# Sheet1.net
KiCad netlist of a schematic drawn in Altium Designer
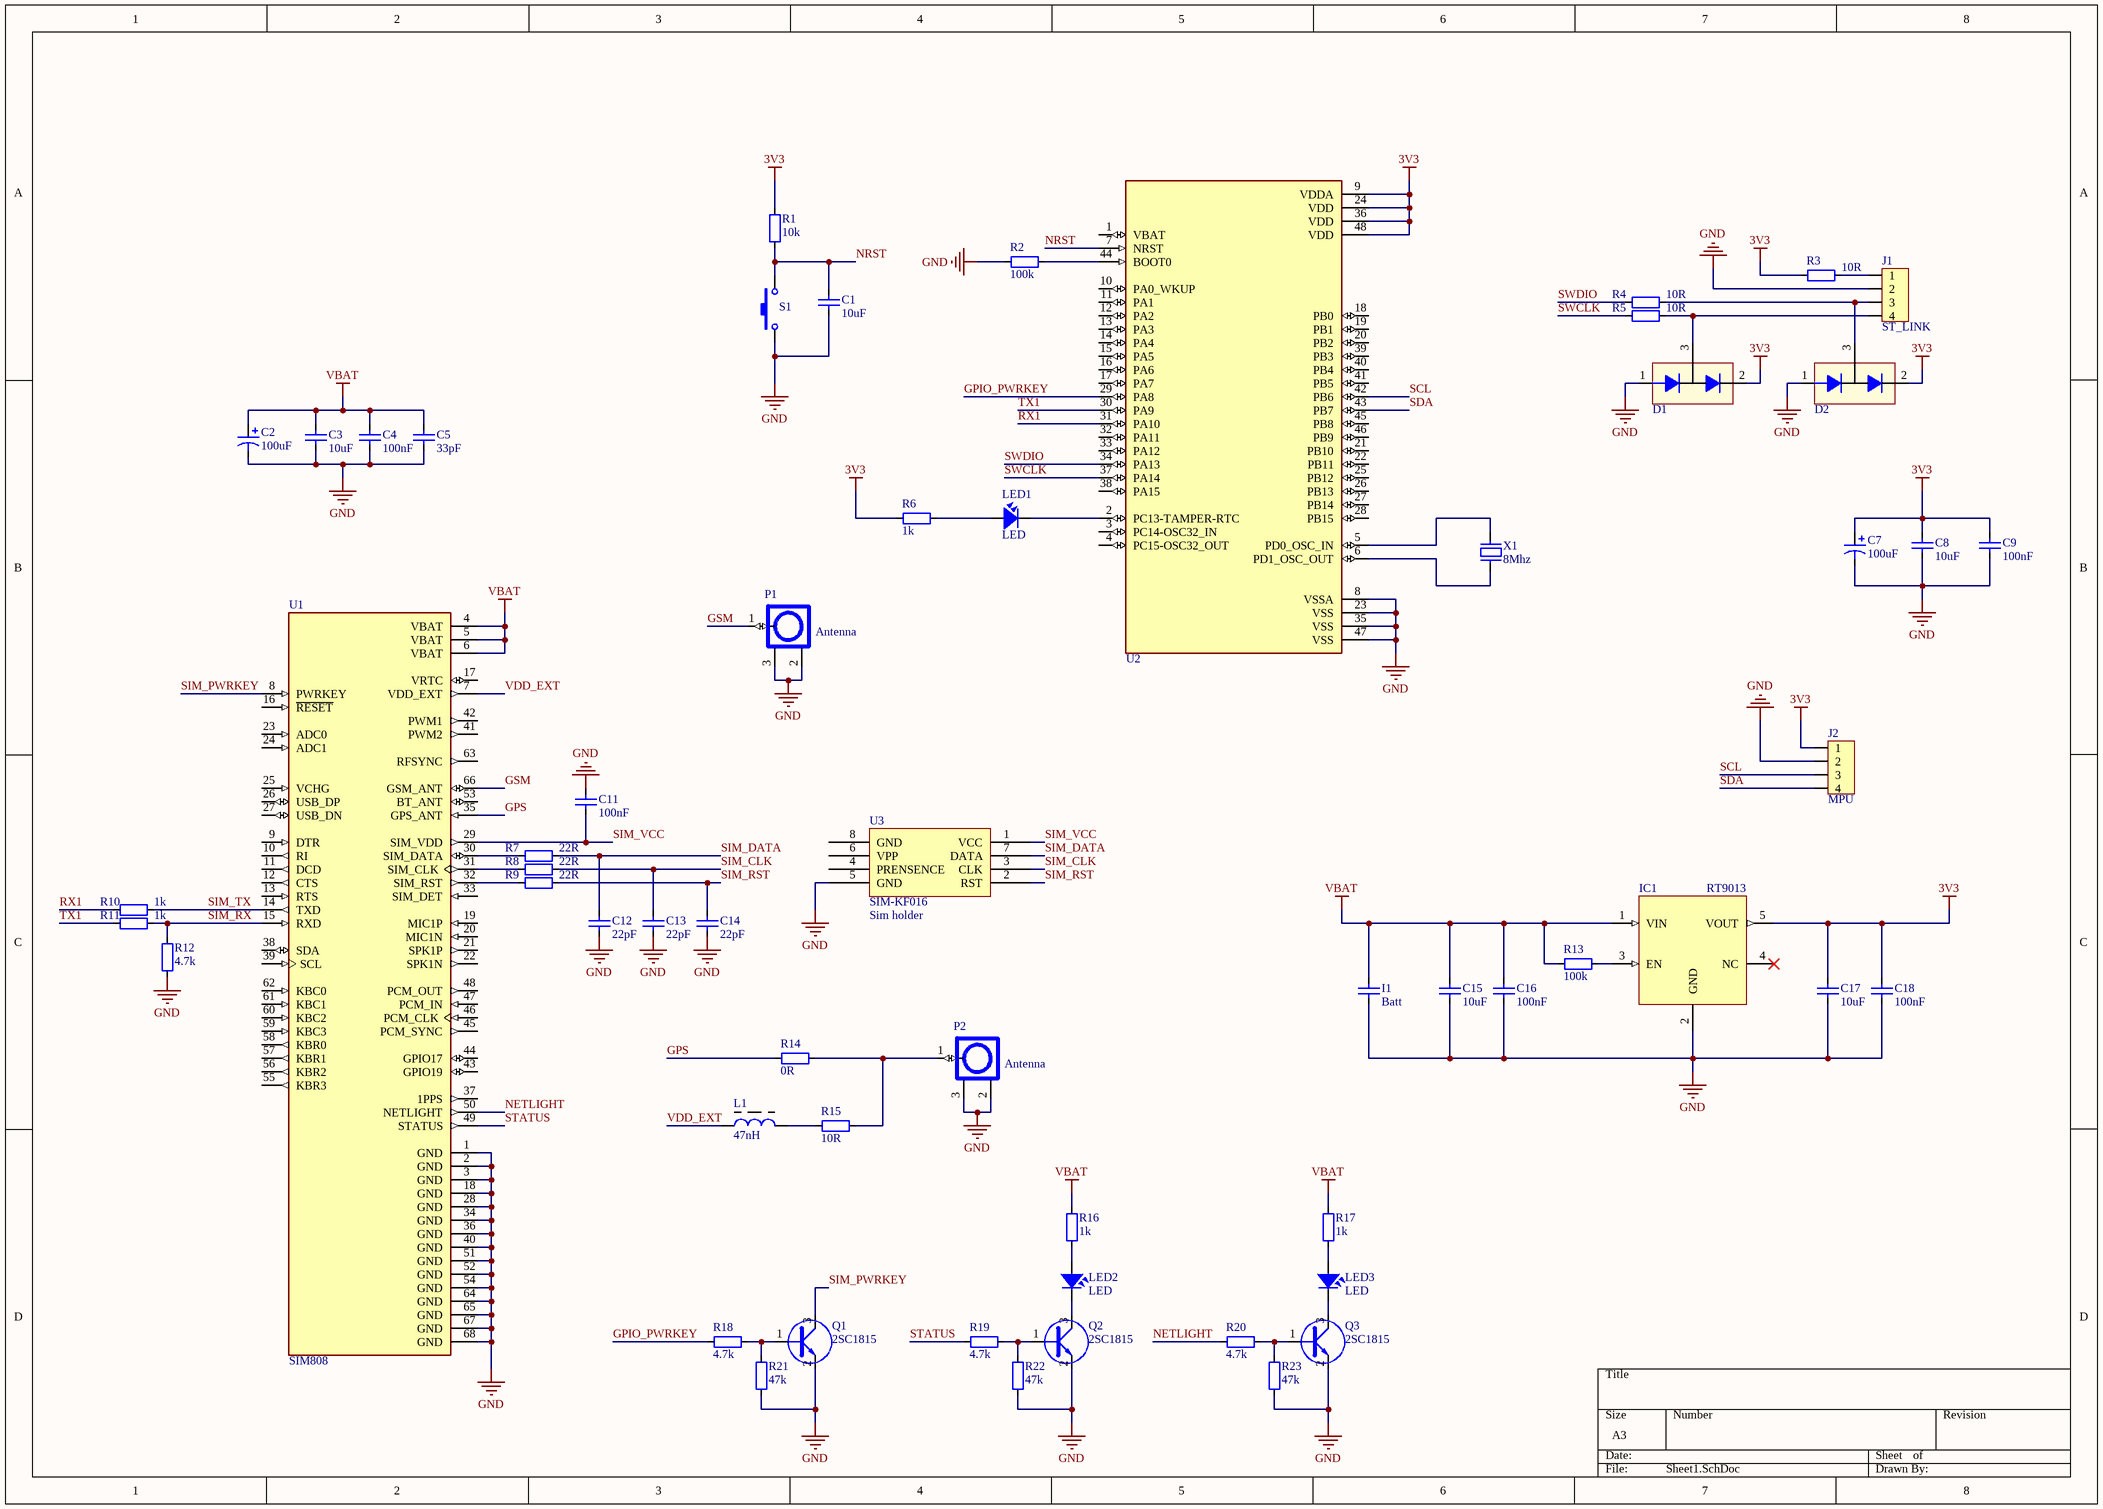
[diagram p0: Sheet1.SchDoc]

(export (version "E")
  (design (tool "Eeschema 10.0.6"))
  (components
    (comp (ref "C1")
      (value "10uF")
      (footprint "CAP_0603")
      (description "Capacitor")
      (fields (field (name "PUBLISHER") "Altium Limited"))
      (libsource (lib "My Library") (part "CapSMD"))
    )
    (comp (ref "C2")
      (value "100uF")
      (footprint "CAP_7343")
      (description "Tantalum")
      (fields (field (name "PUBLISHER") "Altium Limited"))
      (libsource (lib "My Library") (part "Cap Pol"))
    )
    (comp (ref "C3")
      (value "10uF")
      (footprint "CAP_0603")
      (description "Capacitor")
      (fields (field (name "PUBLISHER") "Altium Limited"))
      (libsource (lib "My Library") (part "CapSMD"))
    )
    (comp (ref "C4")
      (value "100nF")
      (footprint "CAP_0603")
      (description "Capacitor")
      (fields (field (name "PUBLISHER") "Altium Limited"))
      (libsource (lib "My Library") (part "CapSMD"))
    )
    (comp (ref "C5")
      (value "33pF")
      (footprint "CAP_0603")
      (description "Capacitor")
      (fields (field (name "PUBLISHER") "Altium Limited"))
      (libsource (lib "My Library") (part "CapSMD"))
    )
    (comp (ref "C7")
      (value "100uF")
      (footprint "CAP_7343")
      (description "Tantalum")
      (fields (field (name "PUBLISHER") "Altium Limited"))
      (libsource (lib "My Library") (part "Cap Pol"))
    )
    (comp (ref "C8")
      (value "10uF")
      (footprint "CAP_0603")
      (description "Capacitor")
      (fields (field (name "PUBLISHER") "Altium Limited"))
      (libsource (lib "My Library") (part "CapSMD"))
    )
    (comp (ref "C9")
      (value "100nF")
      (footprint "CAP_0603")
      (description "Capacitor")
      (fields (field (name "PUBLISHER") "Altium Limited"))
      (libsource (lib "My Library") (part "CapSMD"))
    )
    (comp (ref "C11")
      (value "100nF")
      (footprint "CAP_0603")
      (description "Capacitor")
      (fields (field (name "PUBLISHER") "Altium Limited"))
      (libsource (lib "My Library") (part "CapSMD"))
    )
    (comp (ref "C12")
      (value "22pF")
      (footprint "CAP_0603")
      (description "Capacitor")
      (fields (field (name "PUBLISHER") "Altium Limited"))
      (libsource (lib "My Library") (part "CapSMD"))
    )
    (comp (ref "C13")
      (value "22pF")
      (footprint "CAP_0603")
      (description "Capacitor")
      (fields (field (name "PUBLISHER") "Altium Limited"))
      (libsource (lib "My Library") (part "CapSMD"))
    )
    (comp (ref "C14")
      (value "22pF")
      (footprint "CAP_0603")
      (description "Capacitor")
      (fields (field (name "PUBLISHER") "Altium Limited"))
      (libsource (lib "My Library") (part "CapSMD"))
    )
    (comp (ref "C15")
      (value "10uF")
      (footprint "CAP_0603")
      (description "Capacitor")
      (fields (field (name "PUBLISHER") "Altium Limited"))
      (libsource (lib "My Library") (part "CapSMD"))
    )
    (comp (ref "C16")
      (value "100nF")
      (footprint "CAP_0603")
      (description "Capacitor")
      (fields (field (name "PUBLISHER") "Altium Limited"))
      (libsource (lib "My Library") (part "CapSMD"))
    )
    (comp (ref "C17")
      (value "10uF")
      (footprint "CAP_0603")
      (description "Capacitor")
      (fields (field (name "PUBLISHER") "Altium Limited"))
      (libsource (lib "My Library") (part "CapSMD"))
    )
    (comp (ref "C18")
      (value "100nF")
      (footprint "CAP_0603")
      (description "Capacitor")
      (fields (field (name "PUBLISHER") "Altium Limited"))
      (libsource (lib "My Library") (part "CapSMD"))
    )
    (comp (ref "D1")
      (value "DIODE-BAV99")
      (footprint "SOT23")
      (description "ZENER, SOT23,")
      (fields
        (field (name "MANUFACTURER") "ON Semiconductor / Fairchild")
        (field (name "MANUFACTURER PART NUMBER") "BAV99")
        (field (name ".CREATOR") "LeKhaLinh")
        (field (name ".CHECKPCB") "LeKhaLinh")
        (field (name ".CHECKSCH") "LeKhaLinh")
      )
      (libsource (lib "GPS_Traking_V1_1") (part "DIODE-BAV99"))
    )
    (comp (ref "D2")
      (value "DIODE-BAV99")
      (footprint "SOT23")
      (description "ZENER, SOT23,")
      (fields
        (field (name "MANUFACTURER") "ON Semiconductor / Fairchild")
        (field (name "MANUFACTURER PART NUMBER") "BAV99")
        (field (name ".CREATOR") "LeKhaLinh")
        (field (name ".CHECKPCB") "LeKhaLinh")
        (field (name ".CHECKSCH") "LeKhaLinh")
      )
      (libsource (lib "GPS_Traking_V1_1") (part "DIODE-BAV99"))
    )
    (comp (ref "I1")
      (value "Batt")
      (footprint "CAP_3216")
      (description "Pad")
      (fields (field (name "PUBLISHER") "Altium Limited"))
      (libsource (lib "My Library") (part "CapSMD"))
    )
    (comp (ref "IC1")
      (value "RT9013")
      (footprint "SOT23-5")
      (description "RT9013-33GB IC REG LINEAR 3.3V 500mA SOT23-5")
      (libsource (lib "My Library") (part "RT9013"))
    )
    (comp (ref "J1")
      (value "ST_LINK")
      (footprint "JP4-D1T")
      (description "Header IDC, 4 x 1 Pin Vertical 2.54mm Pitch (Non-Boxed, Male)")
      (fields
        (field (name "MANUFACTURER") "Würth Elektronik eiSos GmbH")
        (field (name "PARTNO") "613002143121")
        (field (name "CREATED BY") "Karrer Zheng")
      )
      (libsource (lib "My Library") (part "Header4"))
    )
    (comp (ref "J2")
      (value "MPU")
      (footprint "JP4-D1T")
      (description "Header IDC, 4 x 1 Pin Vertical 2.54mm Pitch (Non-Boxed, Male)")
      (fields
        (field (name "MANUFACTURER") "Würth Elektronik eiSos GmbH")
        (field (name "PARTNO") "613002143121")
        (field (name "CREATED BY") "Karrer Zheng")
      )
      (libsource (lib "My Library") (part "Header4"))
    )
    (comp (ref "L1")
      (value "47nH")
      (footprint "L-0805")
      (description "Inductor")
      (libsource (lib "My Library") (part "Inductor Ferit"))
    )
    (comp (ref "LED1")
      (value "LED")
      (footprint "LED-0805-Orange")
      (description "LED Single colour Green and Red")
      (libsource (lib "My Library") (part "LED"))
    )
    (comp (ref "LED2")
      (value "LED")
      (footprint "LED-0805-Yellow")
      (description "LED Single colour Green and Red")
      (libsource (lib "My Library") (part "LED"))
    )
    (comp (ref "LED3")
      (value "LED")
      (footprint "LED-0805-Red")
      (description "LED Single colour Green and Red")
      (libsource (lib "My Library") (part "LED"))
    )
    (comp (ref "P1")
      (value "Antenna")
      (footprint "IPXS")
      (description "Antenna GSM GPS")
      (libsource (lib "My Library") (part "IPXSx66"))
    )
    (comp (ref "P2")
      (value "Antenna")
      (footprint "IPXS")
      (description "Antenna GSM GPS")
      (libsource (lib "My Library") (part "IPXSx66"))
    )
    (comp (ref "Q1")
      (value "2SC1815")
      (footprint "SOT23D")
      (description "NPN 600mW, ECB")
      (libsource (lib "My Library") (part "2SC1815"))
    )
    (comp (ref "Q2")
      (value "2SC1815")
      (footprint "SOT23D")
      (description "NPN 600mW, ECB")
      (libsource (lib "My Library") (part "2SC1815"))
    )
    (comp (ref "Q3")
      (value "2SC1815")
      (footprint "SOT23D")
      (description "NPN 600mW, ECB")
      (libsource (lib "My Library") (part "2SC1815"))
    )
    (comp (ref "R1")
      (value "10k")
      (footprint "RES-SMD-0603")
      (description "Resistor")
      (fields
        (field (name "MANUFACTURER") "Generic Components")
        (field (name "PUBLISHER") "Altium Hobart Technology Centre")
      )
      (libsource (lib "My Library") (part "Resistor - SMD"))
    )
    (comp (ref "R2")
      (value "100k")
      (footprint "RES-SMD-0603")
      (description "Resistor")
      (fields
        (field (name "MANUFACTURER") "Generic Components")
        (field (name "PUBLISHER") "Altium Hobart Technology Centre")
      )
      (libsource (lib "My Library") (part "Resistor - SMD"))
    )
    (comp (ref "R3")
      (value "10R")
      (footprint "RES-SMD-0603")
      (description "Resistor")
      (fields
        (field (name "MANUFACTURER") "Generic Components")
        (field (name "PUBLISHER") "Altium Hobart Technology Centre")
      )
      (libsource (lib "My Library") (part "Resistor - SMD"))
    )
    (comp (ref "R4")
      (value "10R")
      (footprint "RES-SMD-0603")
      (description "Resistor")
      (fields
        (field (name "MANUFACTURER") "Generic Components")
        (field (name "PUBLISHER") "Altium Hobart Technology Centre")
      )
      (libsource (lib "My Library") (part "Resistor - SMD"))
    )
    (comp (ref "R5")
      (value "10R")
      (footprint "RES-SMD-0603")
      (description "Resistor")
      (fields
        (field (name "MANUFACTURER") "Generic Components")
        (field (name "PUBLISHER") "Altium Hobart Technology Centre")
      )
      (libsource (lib "My Library") (part "Resistor - SMD"))
    )
    (comp (ref "R6")
      (value "1k")
      (footprint "RES-SMD-0603")
      (description "Resistor")
      (fields
        (field (name "MANUFACTURER") "Generic Components")
        (field (name "PUBLISHER") "Altium Hobart Technology Centre")
      )
      (libsource (lib "My Library") (part "Resistor - SMD"))
    )
    (comp (ref "R7")
      (value "22R")
      (footprint "RES-SMD-0603")
      (description "Resistor")
      (fields
        (field (name "MANUFACTURER") "Generic Components")
        (field (name "PUBLISHER") "Altium Hobart Technology Centre")
      )
      (libsource (lib "My Library") (part "Resistor - SMD"))
    )
    (comp (ref "R8")
      (value "22R")
      (footprint "RES-SMD-0603")
      (description "Resistor")
      (fields
        (field (name "MANUFACTURER") "Generic Components")
        (field (name "PUBLISHER") "Altium Hobart Technology Centre")
      )
      (libsource (lib "My Library") (part "Resistor - SMD"))
    )
    (comp (ref "R9")
      (value "22R")
      (footprint "RES-SMD-0603")
      (description "Resistor")
      (fields
        (field (name "MANUFACTURER") "Generic Components")
        (field (name "PUBLISHER") "Altium Hobart Technology Centre")
      )
      (libsource (lib "My Library") (part "Resistor - SMD"))
    )
    (comp (ref "R10")
      (value "1k")
      (footprint "RES-SMD-0603")
      (description "Resistor")
      (fields
        (field (name "MANUFACTURER") "Generic Components")
        (field (name "PUBLISHER") "Altium Hobart Technology Centre")
      )
      (libsource (lib "My Library") (part "Resistor - SMD"))
    )
    (comp (ref "R11")
      (value "1k")
      (footprint "RES-SMD-0603")
      (description "Resistor")
      (fields
        (field (name "MANUFACTURER") "Generic Components")
        (field (name "PUBLISHER") "Altium Hobart Technology Centre")
      )
      (libsource (lib "My Library") (part "Resistor - SMD"))
    )
    (comp (ref "R12")
      (value "4.7k")
      (footprint "RES-SMD-0603")
      (description "Resistor")
      (fields
        (field (name "MANUFACTURER") "Generic Components")
        (field (name "PUBLISHER") "Altium Hobart Technology Centre")
      )
      (libsource (lib "My Library") (part "Resistor - SMD"))
    )
    (comp (ref "R13")
      (value "100k")
      (footprint "RES-SMD-0603")
      (description "Resistor")
      (fields
        (field (name "MANUFACTURER") "Generic Components")
        (field (name "PUBLISHER") "Altium Hobart Technology Centre")
      )
      (libsource (lib "My Library") (part "Resistor - SMD"))
    )
    (comp (ref "R14")
      (value "0R")
      (footprint "RES-SMD-0805")
      (description "Resistor")
      (fields
        (field (name "MANUFACTURER") "Generic Components")
        (field (name "PUBLISHER") "Altium Hobart Technology Centre")
      )
      (libsource (lib "My Library") (part "Resistor - SMD"))
    )
    (comp (ref "R15")
      (value "10R")
      (footprint "RES-SMD-0805")
      (description "Resistor")
      (fields
        (field (name "MANUFACTURER") "Generic Components")
        (field (name "PUBLISHER") "Altium Hobart Technology Centre")
      )
      (libsource (lib "My Library") (part "Resistor - SMD"))
    )
    (comp (ref "R16")
      (value "1k")
      (footprint "RES-SMD-0603")
      (description "Resistor")
      (fields
        (field (name "MANUFACTURER") "Generic Components")
        (field (name "PUBLISHER") "Altium Hobart Technology Centre")
      )
      (libsource (lib "My Library") (part "Resistor - SMD"))
    )
    (comp (ref "R17")
      (value "1k")
      (footprint "RES-SMD-0603")
      (description "Resistor")
      (fields
        (field (name "MANUFACTURER") "Generic Components")
        (field (name "PUBLISHER") "Altium Hobart Technology Centre")
      )
      (libsource (lib "My Library") (part "Resistor - SMD"))
    )
    (comp (ref "R18")
      (value "4.7k")
      (footprint "RES-SMD-0603")
      (description "Resistor")
      (fields
        (field (name "MANUFACTURER") "Generic Components")
        (field (name "PUBLISHER") "Altium Hobart Technology Centre")
      )
      (libsource (lib "My Library") (part "Resistor - SMD"))
    )
    (comp (ref "R19")
      (value "4.7k")
      (footprint "RES-SMD-0603")
      (description "Resistor")
      (fields
        (field (name "MANUFACTURER") "Generic Components")
        (field (name "PUBLISHER") "Altium Hobart Technology Centre")
      )
      (libsource (lib "My Library") (part "Resistor - SMD"))
    )
    (comp (ref "R20")
      (value "4.7k")
      (footprint "RES-SMD-0603")
      (description "Resistor")
      (fields
        (field (name "MANUFACTURER") "Generic Components")
        (field (name "PUBLISHER") "Altium Hobart Technology Centre")
      )
      (libsource (lib "My Library") (part "Resistor - SMD"))
    )
    (comp (ref "R21")
      (value "47k")
      (footprint "RES-SMD-0603")
      (description "Resistor")
      (fields
        (field (name "MANUFACTURER") "Generic Components")
        (field (name "PUBLISHER") "Altium Hobart Technology Centre")
      )
      (libsource (lib "My Library") (part "Resistor - SMD"))
    )
    (comp (ref "R22")
      (value "47k")
      (footprint "RES-SMD-0603")
      (description "Resistor")
      (fields
        (field (name "MANUFACTURER") "Generic Components")
        (field (name "PUBLISHER") "Altium Hobart Technology Centre")
      )
      (libsource (lib "My Library") (part "Resistor - SMD"))
    )
    (comp (ref "R23")
      (value "47k")
      (footprint "RES-SMD-0603")
      (description "Resistor")
      (fields
        (field (name "MANUFACTURER") "Generic Components")
        (field (name "PUBLISHER") "Altium Hobart Technology Centre")
      )
      (libsource (lib "My Library") (part "Resistor - SMD"))
    )
    (comp (ref "S1")
      (value "SW-SMD")
      (footprint "SW 3x2x4")
      (description "Switch")
      (fields (field (name "PUBLISHER") "Altium Limited"))
      (libsource (lib "My Library") (part "SW-SMD"))
    )
    (comp (ref "U1")
      (value "SIM808")
      (footprint "XCVR_SIM808")
      (description "SIM808 GPS, GPRS/GSM RF Arduino Platform Evaluation Expansion Board")
      (fields (field (name "MF") "Adafruit Industries"))
      (libsource (lib "My Library") (part "SIM808"))
    )
    (comp (ref "U2")
      (value "STM32")
      (footprint "LQFP 48")
      (description "STM32 ARM-based 32-bit MCU with 64 Kbytes Flash, 64-pin LQFP, Industrial Temperature")
      (libsource (lib "My Library") (part "STM32F103C8T6"))
    )
    (comp (ref "U3")
      (value "SIM-KF016")
      (footprint "Sim Socket")
      (description "SIM Card Holder KF-016")
      (fields (field (name "ALTIUM_VALUE") "Sim holder"))
      (libsource (lib "My Library") (part "Sim holder"))
    )
    (comp (ref "X1")
      (value "8Mhz")
      (footprint "XTAL 5032 SMD")
      (description "Crystal For all Crystal 2pin.")
      (libsource (lib "My Library") (part "XT2"))
    )
  )
  (nets
    (net (code "1") (name "/GPIO_PWRKEY") (class "Default")
      (node (ref "R18") (pin "1") (pinfunction "1_1") (pintype "passive"))
      (node (ref "U2") (pin "29") (pinfunction "PA8_29") (pintype "bidirectional"))
    )
    (net (code "2") (name "/GPS") (class "Default")
      (node (ref "R14") (pin "1") (pinfunction "1_1") (pintype "passive"))
      (node (ref "U1") (pin "35") (pinfunction "GPS_ANT_35") (pintype "input"))
    )
    (net (code "3") (name "/GSM") (class "Default")
      (node (ref "P1") (pin "1") (pintype "bidirectional"))
      (node (ref "U1") (pin "66") (pinfunction "GSM_ANT_66") (pintype "bidirectional"))
    )
    (net (code "4") (name "/NETLIGHT") (class "Default")
      (node (ref "R20") (pin "1") (pinfunction "1_1") (pintype "passive"))
      (node (ref "U1") (pin "50") (pinfunction "NETLIGHT_50") (pintype "output"))
    )
    (net (code "5") (name "/NRST") (class "Default")
      (node (ref "C1") (pin "2") (pinfunction "2_2") (pintype "passive"))
      (node (ref "R1") (pin "1") (pinfunction "1_1") (pintype "passive"))
      (node (ref "S1") (pin "2") (pinfunction "2_2") (pintype "passive"))
      (node (ref "U2") (pin "7") (pinfunction "NRST_7") (pintype "input"))
    )
    (net (code "6") (name "/RX1") (class "Default")
      (node (ref "R10") (pin "2") (pinfunction "2_2") (pintype "passive"))
      (node (ref "U2") (pin "31") (pinfunction "PA10_31") (pintype "bidirectional"))
    )
    (net (code "7") (name "/SCL") (class "Default")
      (node (ref "J2") (pin "3") (pinfunction "3_3") (pintype "passive"))
      (node (ref "U2") (pin "42") (pinfunction "PB6_42") (pintype "bidirectional"))
    )
    (net (code "8") (name "/SDA") (class "Default")
      (node (ref "J2") (pin "4") (pinfunction "4_4") (pintype "passive"))
      (node (ref "U2") (pin "43") (pinfunction "PB7_43") (pintype "bidirectional"))
    )
    (net (code "9") (name "/SIM_CLK") (class "Default")
      (node (ref "C13") (pin "1") (pinfunction "1_1") (pintype "passive"))
      (node (ref "R8") (pin "1") (pinfunction "1_1") (pintype "passive"))
      (node (ref "U3") (pin "3") (pinfunction "CLK_3") (pintype "passive"))
    )
    (net (code "10") (name "/SIM_DATA") (class "Default")
      (node (ref "C12") (pin "1") (pinfunction "1_1") (pintype "passive"))
      (node (ref "R7") (pin "1") (pinfunction "1_1") (pintype "passive"))
      (node (ref "U3") (pin "7") (pinfunction "DATA_7") (pintype "passive"))
    )
    (net (code "11") (name "/SIM_PWRKEY") (class "Default")
      (node (ref "Q1") (pin "3") (pinfunction "C_3") (pintype "passive"))
      (node (ref "U1") (pin "8") (pinfunction "PWRKEY_8") (pintype "input"))
    )
    (net (code "12") (name "/SIM_RST") (class "Default")
      (node (ref "C14") (pin "1") (pinfunction "1_1") (pintype "passive"))
      (node (ref "R9") (pin "1") (pinfunction "1_1") (pintype "passive"))
      (node (ref "U3") (pin "2") (pinfunction "RST_2") (pintype "passive"))
    )
    (net (code "13") (name "/SIM_RX") (class "Default")
      (node (ref "R11") (pin "1") (pinfunction "1_1") (pintype "passive"))
      (node (ref "R12") (pin "1") (pinfunction "1_1") (pintype "passive"))
      (node (ref "U1") (pin "15") (pinfunction "RXD_15") (pintype "input"))
    )
    (net (code "14") (name "/SIM_TX") (class "Default")
      (node (ref "R10") (pin "1") (pinfunction "1_1") (pintype "passive"))
      (node (ref "U1") (pin "14") (pinfunction "TXD_14") (pintype "output"))
    )
    (net (code "15") (name "/SIM_VCC") (class "Default")
      (node (ref "C11") (pin "2") (pinfunction "2_2") (pintype "passive"))
      (node (ref "U1") (pin "29") (pinfunction "SIM_VDD_29") (pintype "output"))
      (node (ref "U3") (pin "1") (pinfunction "VCC_1") (pintype "passive"))
    )
    (net (code "16") (name "/STATUS") (class "Default")
      (node (ref "R19") (pin "1") (pinfunction "1_1") (pintype "passive"))
      (node (ref "U1") (pin "49") (pinfunction "STATUS_49") (pintype "output"))
    )
    (net (code "17") (name "/SWCLK") (class "Default")
      (node (ref "R5") (pin "1") (pinfunction "1_1") (pintype "passive"))
      (node (ref "U2") (pin "37") (pinfunction "PA14_37") (pintype "bidirectional"))
    )
    (net (code "18") (name "/SWDIO") (class "Default")
      (node (ref "R4") (pin "1") (pinfunction "1_1") (pintype "passive"))
      (node (ref "U2") (pin "34") (pinfunction "PA13_34") (pintype "bidirectional"))
    )
    (net (code "19") (name "/TX1") (class "Default")
      (node (ref "R11") (pin "2") (pinfunction "2_2") (pintype "passive"))
      (node (ref "U2") (pin "30") (pinfunction "PA9_30") (pintype "bidirectional"))
    )
    (net (code "20") (name "/VDD_EXT") (class "Default")
      (node (ref "L1") (pin "1") (pinfunction "1_1") (pintype "passive"))
      (node (ref "U1") (pin "7") (pinfunction "VDD_EXT_7") (pintype "output"))
    )
    (net (code "21") (name "3V3") (class "Default")
      (node (ref "C17") (pin "2") (pinfunction "2_2") (pintype "passive"))
      (node (ref "C18") (pin "2") (pinfunction "2_2") (pintype "passive"))
      (node (ref "C7") (pin "1") (pinfunction "1_1") (pintype "passive"))
      (node (ref "C8") (pin "2") (pinfunction "2_2") (pintype "passive"))
      (node (ref "C9") (pin "2") (pinfunction "2_2") (pintype "passive"))
      (node (ref "D1") (pin "2") (pinfunction "2_2") (pintype "passive"))
      (node (ref "D2") (pin "2") (pinfunction "2_2") (pintype "passive"))
      (node (ref "IC1") (pin "5") (pinfunction "VOUT_5") (pintype "output"))
      (node (ref "J2") (pin "1") (pinfunction "1_1") (pintype "passive"))
      (node (ref "R1") (pin "2") (pinfunction "2_2") (pintype "passive"))
      (node (ref "R3") (pin "1") (pinfunction "1_1") (pintype "passive"))
      (node (ref "R6") (pin "1") (pinfunction "1_1") (pintype "passive"))
      (node (ref "U2") (pin "24") (pinfunction "VDD_24") (pintype "power_in"))
      (node (ref "U2") (pin "36") (pinfunction "VDD_36") (pintype "power_in"))
      (node (ref "U2") (pin "48") (pinfunction "VDD_48") (pintype "power_in"))
      (node (ref "U2") (pin "9") (pinfunction "VDDA_9") (pintype "power_in"))
    )
    (net (code "22") (name "GND") (class "Default")
      (node (ref "C1") (pin "1") (pinfunction "1_1") (pintype "passive"))
      (node (ref "C11") (pin "1") (pinfunction "1_1") (pintype "passive"))
      (node (ref "C12") (pin "2") (pinfunction "2_2") (pintype "passive"))
      (node (ref "C13") (pin "2") (pinfunction "2_2") (pintype "passive"))
      (node (ref "C14") (pin "2") (pinfunction "2_2") (pintype "passive"))
      (node (ref "C15") (pin "1") (pinfunction "1_1") (pintype "passive"))
      (node (ref "C16") (pin "1") (pinfunction "1_1") (pintype "passive"))
      (node (ref "C17") (pin "1") (pinfunction "1_1") (pintype "passive"))
      (node (ref "C18") (pin "1") (pinfunction "1_1") (pintype "passive"))
      (node (ref "C2") (pin "2") (pinfunction "2_2") (pintype "passive"))
      (node (ref "C3") (pin "1") (pinfunction "1_1") (pintype "passive"))
      (node (ref "C4") (pin "1") (pinfunction "1_1") (pintype "passive"))
      (node (ref "C5") (pin "1") (pinfunction "1_1") (pintype "passive"))
      (node (ref "C7") (pin "2") (pinfunction "2_2") (pintype "passive"))
      (node (ref "C8") (pin "1") (pinfunction "1_1") (pintype "passive"))
      (node (ref "C9") (pin "1") (pinfunction "1_1") (pintype "passive"))
      (node (ref "D1") (pin "1") (pinfunction "1_1") (pintype "passive"))
      (node (ref "D2") (pin "1") (pinfunction "1_1") (pintype "passive"))
      (node (ref "I1") (pin "1") (pinfunction "1_1") (pintype "passive"))
      (node (ref "IC1") (pin "2") (pinfunction "GND_2") (pintype "passive"))
      (node (ref "J1") (pin "2") (pinfunction "2_2") (pintype "passive"))
      (node (ref "J2") (pin "2") (pinfunction "2_2") (pintype "passive"))
      (node (ref "P1") (pin "2") (pintype "passive"))
      (node (ref "P1") (pin "3") (pintype "passive"))
      (node (ref "P2") (pin "2") (pintype "passive"))
      (node (ref "P2") (pin "3") (pintype "passive"))
      (node (ref "Q1") (pin "2") (pinfunction "E_2") (pintype "passive"))
      (node (ref "Q2") (pin "2") (pinfunction "E_2") (pintype "passive"))
      (node (ref "Q3") (pin "2") (pinfunction "E_2") (pintype "passive"))
      (node (ref "R12") (pin "2") (pinfunction "2_2") (pintype "passive"))
      (node (ref "R2") (pin "2") (pinfunction "2_2") (pintype "passive"))
      (node (ref "R21") (pin "1") (pinfunction "1_1") (pintype "passive"))
      (node (ref "R22") (pin "1") (pinfunction "1_1") (pintype "passive"))
      (node (ref "R23") (pin "1") (pinfunction "1_1") (pintype "passive"))
      (node (ref "S1") (pin "1") (pinfunction "1_1") (pintype "passive"))
      (node (ref "U1") (pin "1") (pinfunction "GND_1") (pintype "power_in"))
      (node (ref "U1") (pin "18") (pinfunction "GND_18") (pintype "power_in"))
      (node (ref "U1") (pin "2") (pinfunction "GND_2") (pintype "power_in"))
      (node (ref "U1") (pin "28") (pinfunction "GND_28") (pintype "power_in"))
      (node (ref "U1") (pin "3") (pinfunction "GND_3") (pintype "power_in"))
      (node (ref "U1") (pin "34") (pinfunction "GND_34") (pintype "power_in"))
      (node (ref "U1") (pin "36") (pinfunction "GND_36") (pintype "power_in"))
      (node (ref "U1") (pin "40") (pinfunction "GND_40") (pintype "power_in"))
      (node (ref "U1") (pin "51") (pinfunction "GND_51") (pintype "power_in"))
      (node (ref "U1") (pin "52") (pinfunction "GND_52") (pintype "power_in"))
      (node (ref "U1") (pin "54") (pinfunction "GND_54") (pintype "power_in"))
      (node (ref "U1") (pin "64") (pinfunction "GND_64") (pintype "power_in"))
      (node (ref "U1") (pin "65") (pinfunction "GND_65") (pintype "power_in"))
      (node (ref "U1") (pin "67") (pinfunction "GND_67") (pintype "power_in"))
      (node (ref "U1") (pin "68") (pinfunction "GND_68") (pintype "power_in"))
      (node (ref "U2") (pin "23") (pinfunction "VSS_23") (pintype "power_in"))
      (node (ref "U2") (pin "35") (pinfunction "VSS_35") (pintype "power_in"))
      (node (ref "U2") (pin "47") (pinfunction "VSS_47") (pintype "power_in"))
      (node (ref "U2") (pin "8") (pinfunction "VSSA_8") (pintype "power_in"))
      (node (ref "U3") (pin "5") (pinfunction "GND_5") (pintype "passive"))
    )
    (net (code "23") (name "Net-(D1-Pad3)") (class "Default")
      (node (ref "D1") (pin "3") (pinfunction "3_3") (pintype "passive"))
      (node (ref "J1") (pin "4") (pinfunction "4_4") (pintype "passive"))
      (node (ref "R5") (pin "2") (pinfunction "2_2") (pintype "passive"))
    )
    (net (code "24") (name "Net-(D2-Pad3)") (class "Default")
      (node (ref "D2") (pin "3") (pinfunction "3_3") (pintype "passive"))
      (node (ref "J1") (pin "3") (pinfunction "3_3") (pintype "passive"))
      (node (ref "R4") (pin "2") (pinfunction "2_2") (pintype "passive"))
    )
    (net (code "25") (name "Net-(IC1-EN)") (class "Default")
      (node (ref "IC1") (pin "3") (pinfunction "EN_3") (pintype "input"))
      (node (ref "R13") (pin "1") (pinfunction "1_1") (pintype "passive"))
    )
    (net (code "26") (name "Net-(J1-Pad1)") (class "Default")
      (node (ref "J1") (pin "1") (pinfunction "1_1") (pintype "passive"))
      (node (ref "R3") (pin "2") (pinfunction "2_2") (pintype "passive"))
    )
    (net (code "27") (name "Net-(L1-Pad2)") (class "Default")
      (node (ref "L1") (pin "2") (pinfunction "2_2") (pintype "passive"))
      (node (ref "R15") (pin "2") (pinfunction "2_2") (pintype "passive"))
    )
    (net (code "28") (name "Net-(LED1-Pad1)") (class "Default")
      (node (ref "LED1") (pin "1") (pinfunction "1_1") (pintype "passive"))
      (node (ref "R6") (pin "2") (pinfunction "2_2") (pintype "passive"))
    )
    (net (code "29") (name "Net-(LED2-Pad1)") (class "Default")
      (node (ref "LED2") (pin "1") (pinfunction "1_1") (pintype "passive"))
      (node (ref "R16") (pin "1") (pinfunction "1_1") (pintype "passive"))
    )
    (net (code "30") (name "Net-(LED3-Pad1)") (class "Default")
      (node (ref "LED3") (pin "1") (pinfunction "1_1") (pintype "passive"))
      (node (ref "R17") (pin "1") (pinfunction "1_1") (pintype "passive"))
    )
    (net (code "31") (name "Net-(P2-Pad1)") (class "Default")
      (node (ref "P2") (pin "1") (pintype "bidirectional"))
      (node (ref "R14") (pin "2") (pinfunction "2_2") (pintype "passive"))
      (node (ref "R15") (pin "1") (pinfunction "1_1") (pintype "passive"))
    )
    (net (code "32") (name "Net-(Q1-B)") (class "Default")
      (node (ref "Q1") (pin "1") (pinfunction "B_1") (pintype "passive"))
      (node (ref "R18") (pin "2") (pinfunction "2_2") (pintype "passive"))
      (node (ref "R21") (pin "2") (pinfunction "2_2") (pintype "passive"))
    )
    (net (code "33") (name "Net-(Q2-B)") (class "Default")
      (node (ref "Q2") (pin "1") (pinfunction "B_1") (pintype "passive"))
      (node (ref "R19") (pin "2") (pinfunction "2_2") (pintype "passive"))
      (node (ref "R22") (pin "2") (pinfunction "2_2") (pintype "passive"))
    )
    (net (code "34") (name "Net-(Q2-C)") (class "Default")
      (node (ref "LED2") (pin "2") (pinfunction "2_2") (pintype "passive"))
      (node (ref "Q2") (pin "3") (pinfunction "C_3") (pintype "passive"))
    )
    (net (code "35") (name "Net-(Q3-B)") (class "Default")
      (node (ref "Q3") (pin "1") (pinfunction "B_1") (pintype "passive"))
      (node (ref "R20") (pin "2") (pinfunction "2_2") (pintype "passive"))
      (node (ref "R23") (pin "2") (pinfunction "2_2") (pintype "passive"))
    )
    (net (code "36") (name "Net-(Q3-C)") (class "Default")
      (node (ref "LED3") (pin "2") (pinfunction "2_2") (pintype "passive"))
      (node (ref "Q3") (pin "3") (pinfunction "C_3") (pintype "passive"))
    )
    (net (code "37") (name "Net-(U1-SIM_CLK)") (class "Default")
      (node (ref "R8") (pin "2") (pinfunction "2_2") (pintype "passive"))
      (node (ref "U1") (pin "31") (pinfunction "SIM_CLK_31") (pintype "output"))
    )
    (net (code "38") (name "Net-(U1-SIM_DATA)") (class "Default")
      (node (ref "R7") (pin "2") (pinfunction "2_2") (pintype "passive"))
      (node (ref "U1") (pin "30") (pinfunction "SIM_DATA_30") (pintype "bidirectional"))
    )
    (net (code "39") (name "Net-(U1-SIM_RST)") (class "Default")
      (node (ref "R9") (pin "2") (pinfunction "2_2") (pintype "passive"))
      (node (ref "U1") (pin "32") (pinfunction "SIM_RST_32") (pintype "output"))
    )
    (net (code "40") (name "Net-(U2-BOOT0)") (class "Default")
      (node (ref "R2") (pin "1") (pinfunction "1_1") (pintype "passive"))
      (node (ref "U2") (pin "44") (pinfunction "BOOT0_44") (pintype "input"))
    )
    (net (code "41") (name "Net-(U2-PC13-TAMPER-RTC)") (class "Default")
      (node (ref "LED1") (pin "2") (pinfunction "2_2") (pintype "passive"))
      (node (ref "U2") (pin "2") (pinfunction "PC13-TAMPER-RTC_2") (pintype "bidirectional"))
    )
    (net (code "42") (name "Net-(U2-PD0_OSC_IN)") (class "Default")
      (node (ref "U2") (pin "5") (pinfunction "PD0_OSC_IN_5") (pintype "bidirectional"))
      (node (ref "X1") (pin "2") (pinfunction "2_2") (pintype "passive"))
    )
    (net (code "43") (name "Net-(U2-PD1_OSC_OUT)") (class "Default")
      (node (ref "U2") (pin "6") (pinfunction "PD1_OSC_OUT_6") (pintype "bidirectional"))
      (node (ref "X1") (pin "1") (pinfunction "1_1") (pintype "passive"))
    )
    (net (code "44") (name "VBAT") (class "Default")
      (node (ref "C15") (pin "2") (pinfunction "2_2") (pintype "passive"))
      (node (ref "C16") (pin "2") (pinfunction "2_2") (pintype "passive"))
      (node (ref "C2") (pin "1") (pinfunction "1_1") (pintype "passive"))
      (node (ref "C3") (pin "2") (pinfunction "2_2") (pintype "passive"))
      (node (ref "C4") (pin "2") (pinfunction "2_2") (pintype "passive"))
      (node (ref "C5") (pin "2") (pinfunction "2_2") (pintype "passive"))
      (node (ref "I1") (pin "2") (pinfunction "2_2") (pintype "passive"))
      (node (ref "IC1") (pin "1") (pinfunction "VIN_1") (pintype "input"))
      (node (ref "R13") (pin "2") (pinfunction "2_2") (pintype "passive"))
      (node (ref "R16") (pin "2") (pinfunction "2_2") (pintype "passive"))
      (node (ref "R17") (pin "2") (pinfunction "2_2") (pintype "passive"))
      (node (ref "U1") (pin "4") (pinfunction "VBAT_4") (pintype "power_in"))
      (node (ref "U1") (pin "5") (pinfunction "VBAT_5") (pintype "power_in"))
      (node (ref "U1") (pin "6") (pinfunction "VBAT_6") (pintype "power_in"))
    )
    (net (code "45") (name "unconnected-(IC1-NC-Pad4)") (class "Default")
      (node (ref "IC1") (pin "4") (pinfunction "NC_4") (pintype "passive+no_connect"))
    )
    (net (code "46") (name "unconnected-(U1-1PPS-Pad37)") (class "Default")
      (node (ref "U1") (pin "37") (pinfunction "1PPS_37") (pintype "output"))
    )
    (net (code "47") (name "unconnected-(U1-ADC0-Pad23)") (class "Default")
      (node (ref "U1") (pin "23") (pinfunction "ADC0_23") (pintype "input"))
    )
    (net (code "48") (name "unconnected-(U1-ADC1-Pad24)") (class "Default")
      (node (ref "U1") (pin "24") (pinfunction "ADC1_24") (pintype "input"))
    )
    (net (code "49") (name "unconnected-(U1-BT_ANT-Pad53)") (class "Default")
      (node (ref "U1") (pin "53") (pinfunction "BT_ANT_53") (pintype "bidirectional"))
    )
    (net (code "50") (name "unconnected-(U1-CTS-Pad12)") (class "Default")
      (node (ref "U1") (pin "12") (pinfunction "CTS_12") (pintype "output"))
    )
    (net (code "51") (name "unconnected-(U1-DCD-Pad11)") (class "Default")
      (node (ref "U1") (pin "11") (pinfunction "DCD_11") (pintype "output"))
    )
    (net (code "52") (name "unconnected-(U1-DTR-Pad9)") (class "Default")
      (node (ref "U1") (pin "9") (pinfunction "DTR_9") (pintype "input"))
    )
    (net (code "53") (name "unconnected-(U1-GPIO17-Pad44)") (class "Default")
      (node (ref "U1") (pin "44") (pinfunction "GPIO17_44") (pintype "bidirectional"))
    )
    (net (code "54") (name "unconnected-(U1-GPIO19-Pad43)") (class "Default")
      (node (ref "U1") (pin "43") (pinfunction "GPIO19_43") (pintype "bidirectional"))
    )
    (net (code "55") (name "unconnected-(U1-KBC0-Pad62)") (class "Default")
      (node (ref "U1") (pin "62") (pinfunction "KBC0_62") (pintype "input"))
    )
    (net (code "56") (name "unconnected-(U1-KBC1-Pad61)") (class "Default")
      (node (ref "U1") (pin "61") (pinfunction "KBC1_61") (pintype "input"))
    )
    (net (code "57") (name "unconnected-(U1-KBC2-Pad60)") (class "Default")
      (node (ref "U1") (pin "60") (pinfunction "KBC2_60") (pintype "input"))
    )
    (net (code "58") (name "unconnected-(U1-KBC3-Pad59)") (class "Default")
      (node (ref "U1") (pin "59") (pinfunction "KBC3_59") (pintype "input"))
    )
    (net (code "59") (name "unconnected-(U1-KBR0-Pad58)") (class "Default")
      (node (ref "U1") (pin "58") (pinfunction "KBR0_58") (pintype "output"))
    )
    (net (code "60") (name "unconnected-(U1-KBR1-Pad57)") (class "Default")
      (node (ref "U1") (pin "57") (pinfunction "KBR1_57") (pintype "output"))
    )
    (net (code "61") (name "unconnected-(U1-KBR2-Pad56)") (class "Default")
      (node (ref "U1") (pin "56") (pinfunction "KBR2_56") (pintype "output"))
    )
    (net (code "62") (name "unconnected-(U1-KBR3-Pad55)") (class "Default")
      (node (ref "U1") (pin "55") (pinfunction "KBR3_55") (pintype "output"))
    )
    (net (code "63") (name "unconnected-(U1-MIC1N-Pad20)") (class "Default")
      (node (ref "U1") (pin "20") (pinfunction "MIC1N_20") (pintype "input"))
    )
    (net (code "64") (name "unconnected-(U1-MIC1P-Pad19)") (class "Default")
      (node (ref "U1") (pin "19") (pinfunction "MIC1P_19") (pintype "input"))
    )
    (net (code "65") (name "unconnected-(U1-PCM_CLK-Pad46)") (class "Default")
      (node (ref "U1") (pin "46") (pinfunction "PCM_CLK_46") (pintype "input"))
    )
    (net (code "66") (name "unconnected-(U1-PCM_IN-Pad47)") (class "Default")
      (node (ref "U1") (pin "47") (pinfunction "PCM_IN_47") (pintype "input"))
    )
    (net (code "67") (name "unconnected-(U1-PCM_OUT-Pad48)") (class "Default")
      (node (ref "U1") (pin "48") (pinfunction "PCM_OUT_48") (pintype "output"))
    )
    (net (code "68") (name "unconnected-(U1-PCM_SYNC-Pad45)") (class "Default")
      (node (ref "U1") (pin "45") (pinfunction "PCM_SYNC_45") (pintype "output"))
    )
    (net (code "69") (name "unconnected-(U1-PWM1-Pad42)") (class "Default")
      (node (ref "U1") (pin "42") (pinfunction "PWM1_42") (pintype "output"))
    )
    (net (code "70") (name "unconnected-(U1-PWM2-Pad41)") (class "Default")
      (node (ref "U1") (pin "41") (pinfunction "PWM2_41") (pintype "output"))
    )
    (net (code "71") (name "unconnected-(U1-RFSYNC-Pad63)") (class "Default")
      (node (ref "U1") (pin "63") (pinfunction "RFSYNC_63") (pintype "output"))
    )
    (net (code "72") (name "unconnected-(U1-RI-Pad10)") (class "Default")
      (node (ref "U1") (pin "10") (pinfunction "RI_10") (pintype "output"))
    )
    (net (code "73") (name "unconnected-(U1-RTS-Pad13)") (class "Default")
      (node (ref "U1") (pin "13") (pinfunction "RTS_13") (pintype "input"))
    )
    (net (code "74") (name "unconnected-(U1-SCL-Pad39)") (class "Default")
      (node (ref "U1") (pin "39") (pinfunction "SCL_39") (pintype "input"))
    )
    (net (code "75") (name "unconnected-(U1-SDA-Pad38)") (class "Default")
      (node (ref "U1") (pin "38") (pinfunction "SDA_38") (pintype "bidirectional"))
    )
    (net (code "76") (name "unconnected-(U1-SIM_DET-Pad33)") (class "Default")
      (node (ref "U1") (pin "33") (pinfunction "SIM_DET_33") (pintype "input"))
    )
    (net (code "77") (name "unconnected-(U1-SPK1N-Pad22)") (class "Default")
      (node (ref "U1") (pin "22") (pinfunction "SPK1N_22") (pintype "output"))
    )
    (net (code "78") (name "unconnected-(U1-SPK1P-Pad21)") (class "Default")
      (node (ref "U1") (pin "21") (pinfunction "SPK1P_21") (pintype "output"))
    )
    (net (code "79") (name "unconnected-(U1-USB_DN-Pad27)") (class "Default")
      (node (ref "U1") (pin "27") (pinfunction "USB_DN_27") (pintype "bidirectional"))
    )
    (net (code "80") (name "unconnected-(U1-USB_DP-Pad26)") (class "Default")
      (node (ref "U1") (pin "26") (pinfunction "USB_DP_26") (pintype "bidirectional"))
    )
    (net (code "81") (name "unconnected-(U1-VCHG-Pad25)") (class "Default")
      (node (ref "U1") (pin "25") (pinfunction "VCHG_25") (pintype "input"))
    )
    (net (code "82") (name "unconnected-(U1-VRTC-Pad17)") (class "Default")
      (node (ref "U1") (pin "17") (pinfunction "VRTC_17") (pintype "bidirectional"))
    )
    (net (code "83") (name "unconnected-(U1-~{RESET}-Pad16)") (class "Default")
      (node (ref "U1") (pin "16") (pinfunction "~{RESET}_16") (pintype "input"))
    )
    (net (code "84") (name "unconnected-(U2-PA0_WKUP-Pad10)") (class "Default")
      (node (ref "U2") (pin "10") (pinfunction "PA0_WKUP_10") (pintype "bidirectional"))
    )
    (net (code "85") (name "unconnected-(U2-PA1-Pad11)") (class "Default")
      (node (ref "U2") (pin "11") (pinfunction "PA1_11") (pintype "bidirectional"))
    )
    (net (code "86") (name "unconnected-(U2-PA2-Pad12)") (class "Default")
      (node (ref "U2") (pin "12") (pinfunction "PA2_12") (pintype "bidirectional"))
    )
    (net (code "87") (name "unconnected-(U2-PA3-Pad13)") (class "Default")
      (node (ref "U2") (pin "13") (pinfunction "PA3_13") (pintype "bidirectional"))
    )
    (net (code "88") (name "unconnected-(U2-PA4-Pad14)") (class "Default")
      (node (ref "U2") (pin "14") (pinfunction "PA4_14") (pintype "bidirectional"))
    )
    (net (code "89") (name "unconnected-(U2-PA5-Pad15)") (class "Default")
      (node (ref "U2") (pin "15") (pinfunction "PA5_15") (pintype "bidirectional"))
    )
    (net (code "90") (name "unconnected-(U2-PA6-Pad16)") (class "Default")
      (node (ref "U2") (pin "16") (pinfunction "PA6_16") (pintype "bidirectional"))
    )
    (net (code "91") (name "unconnected-(U2-PA7-Pad17)") (class "Default")
      (node (ref "U2") (pin "17") (pinfunction "PA7_17") (pintype "bidirectional"))
    )
    (net (code "92") (name "unconnected-(U2-PA11-Pad32)") (class "Default")
      (node (ref "U2") (pin "32") (pinfunction "PA11_32") (pintype "bidirectional"))
    )
    (net (code "93") (name "unconnected-(U2-PA12-Pad33)") (class "Default")
      (node (ref "U2") (pin "33") (pinfunction "PA12_33") (pintype "bidirectional"))
    )
    (net (code "94") (name "unconnected-(U2-PA15-Pad38)") (class "Default")
      (node (ref "U2") (pin "38") (pinfunction "PA15_38") (pintype "bidirectional"))
    )
    (net (code "95") (name "unconnected-(U2-PB0-Pad18)") (class "Default")
      (node (ref "U2") (pin "18") (pinfunction "PB0_18") (pintype "bidirectional"))
    )
    (net (code "96") (name "unconnected-(U2-PB1-Pad19)") (class "Default")
      (node (ref "U2") (pin "19") (pinfunction "PB1_19") (pintype "bidirectional"))
    )
    (net (code "97") (name "unconnected-(U2-PB2-Pad20)") (class "Default")
      (node (ref "U2") (pin "20") (pinfunction "PB2_20") (pintype "bidirectional"))
    )
    (net (code "98") (name "unconnected-(U2-PB3-Pad39)") (class "Default")
      (node (ref "U2") (pin "39") (pinfunction "PB3_39") (pintype "bidirectional"))
    )
    (net (code "99") (name "unconnected-(U2-PB4-Pad40)") (class "Default")
      (node (ref "U2") (pin "40") (pinfunction "PB4_40") (pintype "bidirectional"))
    )
    (net (code "100") (name "unconnected-(U2-PB5-Pad41)") (class "Default")
      (node (ref "U2") (pin "41") (pinfunction "PB5_41") (pintype "bidirectional"))
    )
    (net (code "101") (name "unconnected-(U2-PB8-Pad45)") (class "Default")
      (node (ref "U2") (pin "45") (pinfunction "PB8_45") (pintype "bidirectional"))
    )
    (net (code "102") (name "unconnected-(U2-PB9-Pad46)") (class "Default")
      (node (ref "U2") (pin "46") (pinfunction "PB9_46") (pintype "bidirectional"))
    )
    (net (code "103") (name "unconnected-(U2-PB10-Pad21)") (class "Default")
      (node (ref "U2") (pin "21") (pinfunction "PB10_21") (pintype "bidirectional"))
    )
    (net (code "104") (name "unconnected-(U2-PB11-Pad22)") (class "Default")
      (node (ref "U2") (pin "22") (pinfunction "PB11_22") (pintype "bidirectional"))
    )
    (net (code "105") (name "unconnected-(U2-PB12-Pad25)") (class "Default")
      (node (ref "U2") (pin "25") (pinfunction "PB12_25") (pintype "bidirectional"))
    )
    (net (code "106") (name "unconnected-(U2-PB13-Pad26)") (class "Default")
      (node (ref "U2") (pin "26") (pinfunction "PB13_26") (pintype "bidirectional"))
    )
    (net (code "107") (name "unconnected-(U2-PB14-Pad27)") (class "Default")
      (node (ref "U2") (pin "27") (pinfunction "PB14_27") (pintype "bidirectional"))
    )
    (net (code "108") (name "unconnected-(U2-PB15-Pad28)") (class "Default")
      (node (ref "U2") (pin "28") (pinfunction "PB15_28") (pintype "bidirectional"))
    )
    (net (code "109") (name "unconnected-(U2-PC14-OSC32_IN-Pad3)") (class "Default")
      (node (ref "U2") (pin "3") (pinfunction "PC14-OSC32_IN_3") (pintype "bidirectional"))
    )
    (net (code "110") (name "unconnected-(U2-PC15-OSC32_OUT-Pad4)") (class "Default")
      (node (ref "U2") (pin "4") (pinfunction "PC15-OSC32_OUT_4") (pintype "bidirectional"))
    )
    (net (code "111") (name "unconnected-(U2-VBAT-Pad1)") (class "Default")
      (node (ref "U2") (pin "1") (pinfunction "VBAT_1") (pintype "bidirectional"))
    )
    (net (code "112") (name "unconnected-(U3-GND-Pad8)") (class "Default")
      (node (ref "U3") (pin "8") (pinfunction "GND_8") (pintype "passive"))
    )
    (net (code "113") (name "unconnected-(U3-PRENSENCE-Pad4)") (class "Default")
      (node (ref "U3") (pin "4") (pinfunction "PRENSENCE_4") (pintype "passive"))
    )
    (net (code "114") (name "unconnected-(U3-VPP-Pad6)") (class "Default")
      (node (ref "U3") (pin "6") (pinfunction "VPP_6") (pintype "passive"))
    )
  )
)
